# cpu.net
KiCad netlist of a schematic drawn in Altium Designer
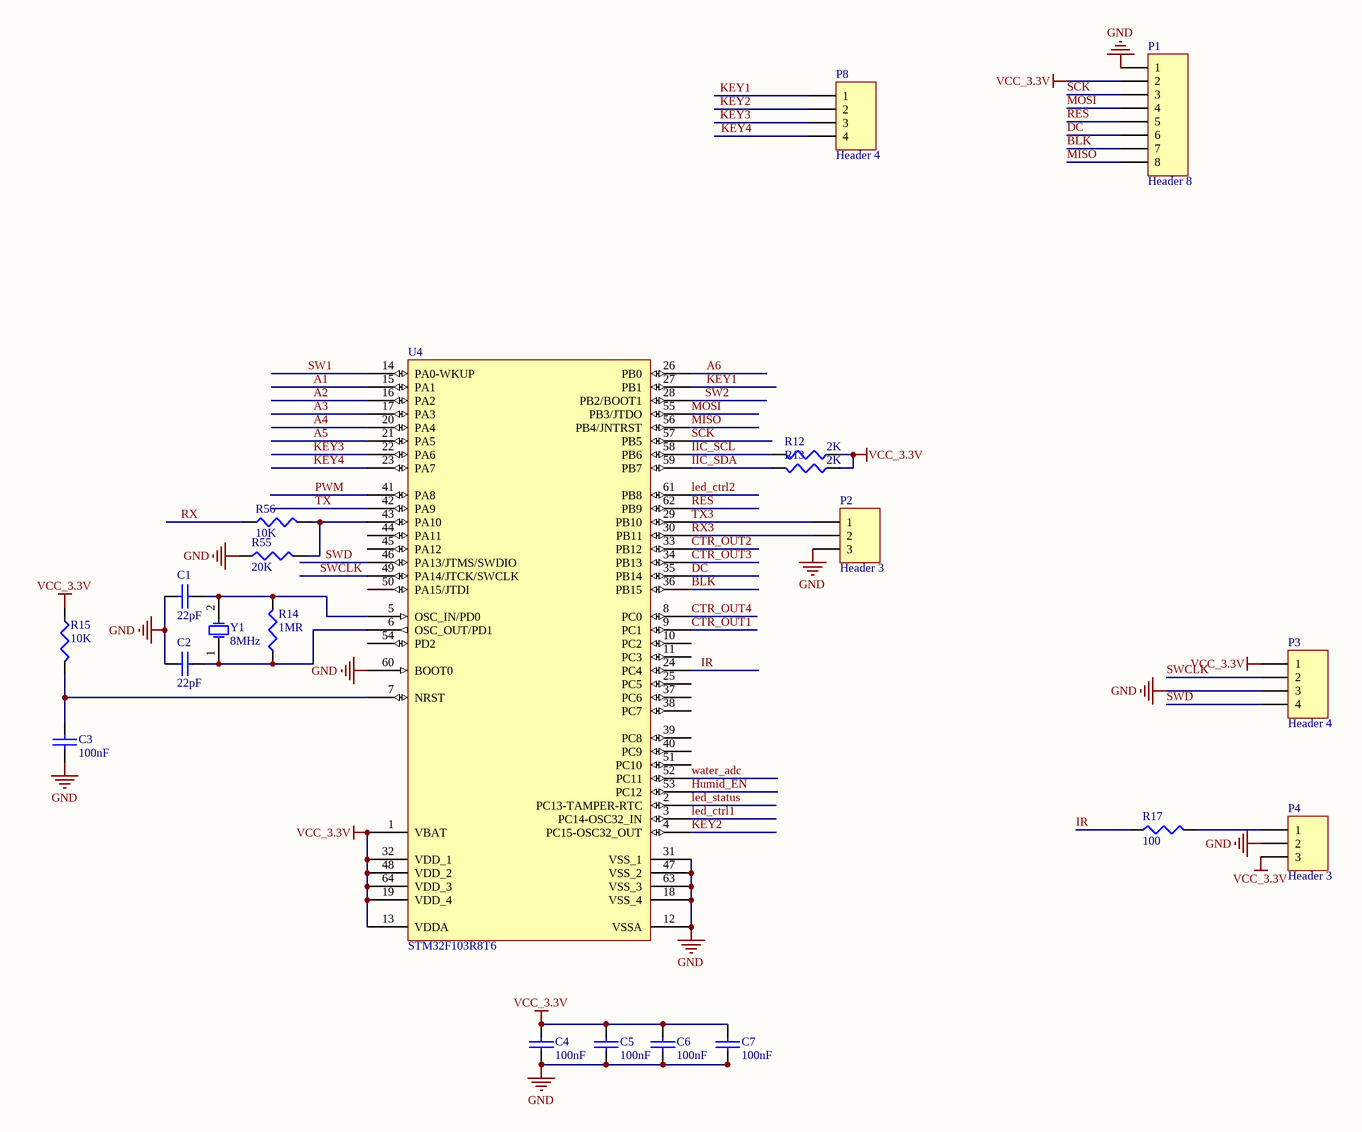
[diagram p0: cpu.SchDoc]

(export (version "E")
  (design (tool "Eeschema 10.0.6"))
  (components
    (comp (ref "C1")
      (value "22pF")
      (footprint "0805c")
      (description "Capacitor")
      (libsource (lib "SM") (part "CAP"))
    )
    (comp (ref "C2")
      (value "22pF")
      (footprint "0805c")
      (description "Capacitor")
      (libsource (lib "SM") (part "CAP"))
    )
    (comp (ref "C3")
      (value "100nF")
      (footprint "0805c")
      (description "Capacitor")
      (libsource (lib "SM") (part "CAP"))
    )
    (comp (ref "C4")
      (value "100nF")
      (footprint "0805c")
      (description "Capacitor")
      (libsource (lib "SM") (part "CAP"))
    )
    (comp (ref "C5")
      (value "100nF")
      (footprint "0805c")
      (description "Capacitor")
      (libsource (lib "SM") (part "CAP"))
    )
    (comp (ref "C6")
      (value "100nF")
      (footprint "0805c")
      (description "Capacitor")
      (libsource (lib "SM") (part "CAP"))
    )
    (comp (ref "C7")
      (value "100nF")
      (footprint "0805c")
      (description "Capacitor")
      (libsource (lib "SM") (part "CAP"))
    )
    (comp (ref "P1")
      (value "Header 8")
      (footprint "HDR1X8")
      (description "Header, 8-Pin")
      (fields (field (name "PUBLISHER") "Altium Limited"))
      (libsource (lib "Miscellaneous Connectors") (part "Header 8"))
    )
    (comp (ref "P2")
      (value "Header 3")
      (footprint "HDR1X3")
      (description "Header, 3-Pin")
      (fields (field (name "PUBLISHER") "Altium Limited"))
      (libsource (lib "Miscellaneous Connectors") (part "Header 3"))
    )
    (comp (ref "P3")
      (value "Header 4")
      (footprint "HDR1X4")
      (description "Header, 4-Pin")
      (fields (field (name "PUBLISHER") "Altium Limited"))
      (libsource (lib "Miscellaneous Connectors") (part "Header 4"))
    )
    (comp (ref "P4")
      (value "Header 3")
      (footprint "HDR1X3")
      (description "Header, 3-Pin")
      (fields (field (name "PUBLISHER") "Altium Limited"))
      (libsource (lib "Miscellaneous Connectors") (part "Header 3"))
    )
    (comp (ref "P8")
      (value "Header 4")
      (footprint "HDR1X4")
      (description "Header, 4-Pin")
      (fields (field (name "PUBLISHER") "Altium Limited"))
      (libsource (lib "Miscellaneous Connectors") (part "Header 4"))
    )
    (comp (ref "R12")
      (value "2K")
      (footprint "0805R")
      (description "Resistor")
      (fields (field (name "PUBLISHER") "Altium Limited"))
      (libsource (lib "SM") (part "Res3"))
    )
    (comp (ref "R13")
      (value "2K")
      (footprint "0805R")
      (description "Resistor")
      (fields (field (name "PUBLISHER") "Altium Limited"))
      (libsource (lib "SM") (part "Res3"))
    )
    (comp (ref "R14")
      (value "1MR")
      (footprint "0805R")
      (description "Resistor")
      (fields (field (name "PUBLISHER") "Altium Limited"))
      (libsource (lib "SM") (part "Res3"))
    )
    (comp (ref "R15")
      (value "10K")
      (footprint "0805R")
      (description "Resistor")
      (fields (field (name "PUBLISHER") "Altium Limited"))
      (libsource (lib "SM") (part "Res3"))
    )
    (comp (ref "R17")
      (value "100")
      (footprint "0805R")
      (description "Resistor")
      (fields (field (name "PUBLISHER") "Altium Limited"))
      (libsource (lib "SM") (part "Res3"))
    )
    (comp (ref "R55")
      (value "20K")
      (footprint "0805R")
      (description "Resistor")
      (fields (field (name "PUBLISHER") "Altium Limited"))
      (libsource (lib "SM") (part "Res3"))
    )
    (comp (ref "R56")
      (value "10K")
      (footprint "0805R")
      (description "Resistor")
      (fields (field (name "PUBLISHER") "Altium Limited"))
      (libsource (lib "SM") (part "Res3"))
    )
    (comp (ref "U4")
      (value "STM32F103R8T6")
      (footprint "LQFP-64")
      (description "STM32 ARM-based 32-bit MCU with 64 Kbytes Flash, 64-pin LQFP, Industrial Temperature")
      (fields (field (name "PUBLISHER") "Altium Limited"))
      (libsource (lib "ST Microcontroller 32-Bit STM32") (part "STM32F103R8T6"))
    )
    (comp (ref "Y1")
      (value "8MHz")
      (footprint "SMT5032")
      (description "Crystal Oscillator")
      (fields (field (name "PUBLISHER") "Altium Limited"))
      (libsource (lib "Miscellaneous Devices") (part "XTAL"))
    )
  )
  (nets
    (net (code "1") (name "/A1") (class "Default")
      (node (ref "U4") (pin "15") (pinfunction "PA1_15") (pintype "bidirectional"))
    )
    (net (code "2") (name "/A2") (class "Default")
      (node (ref "U4") (pin "16") (pinfunction "PA2_16") (pintype "bidirectional"))
    )
    (net (code "3") (name "/A3") (class "Default")
      (node (ref "U4") (pin "17") (pinfunction "PA3_17") (pintype "bidirectional"))
    )
    (net (code "4") (name "/A4") (class "Default")
      (node (ref "U4") (pin "20") (pinfunction "PA4_20") (pintype "bidirectional"))
    )
    (net (code "5") (name "/A5") (class "Default")
      (node (ref "U4") (pin "21") (pinfunction "PA5_21") (pintype "bidirectional"))
    )
    (net (code "6") (name "/A6") (class "Default")
      (node (ref "U4") (pin "26") (pinfunction "PB0_26") (pintype "bidirectional"))
    )
    (net (code "7") (name "/BLK") (class "Default")
      (node (ref "P1") (pin "7") (pinfunction "7_7") (pintype "passive"))
      (node (ref "U4") (pin "36") (pinfunction "PB15_36") (pintype "bidirectional"))
    )
    (net (code "8") (name "/CTR_OUT1") (class "Default")
      (node (ref "U4") (pin "9") (pinfunction "PC1_9") (pintype "bidirectional"))
    )
    (net (code "9") (name "/CTR_OUT2") (class "Default")
      (node (ref "U4") (pin "33") (pinfunction "PB12_33") (pintype "bidirectional"))
    )
    (net (code "10") (name "/CTR_OUT3") (class "Default")
      (node (ref "U4") (pin "34") (pinfunction "PB13_34") (pintype "bidirectional"))
    )
    (net (code "11") (name "/CTR_OUT4") (class "Default")
      (node (ref "U4") (pin "8") (pinfunction "PC0_8") (pintype "bidirectional"))
    )
    (net (code "12") (name "/DC") (class "Default")
      (node (ref "P1") (pin "6") (pinfunction "6_6") (pintype "passive"))
      (node (ref "U4") (pin "35") (pinfunction "PB14_35") (pintype "bidirectional"))
    )
    (net (code "13") (name "/Humid_EN") (class "Default")
      (node (ref "U4") (pin "53") (pinfunction "PC12_53") (pintype "bidirectional"))
    )
    (net (code "14") (name "/IIC_SCL") (class "Default")
      (node (ref "R12") (pin "2") (pinfunction "2_2") (pintype "passive"))
      (node (ref "U4") (pin "58") (pinfunction "PB6_58") (pintype "bidirectional"))
    )
    (net (code "15") (name "/IIC_SDA") (class "Default")
      (node (ref "R13") (pin "2") (pinfunction "2_2") (pintype "passive"))
      (node (ref "U4") (pin "59") (pinfunction "PB7_59") (pintype "bidirectional"))
    )
    (net (code "16") (name "/IR") (class "Default")
      (node (ref "R17") (pin "1") (pinfunction "1_1") (pintype "passive"))
      (node (ref "U4") (pin "24") (pinfunction "PC4_24") (pintype "bidirectional"))
    )
    (net (code "17") (name "/KEY1") (class "Default")
      (node (ref "P8") (pin "1") (pinfunction "1_1") (pintype "passive"))
      (node (ref "U4") (pin "27") (pinfunction "PB1_27") (pintype "bidirectional"))
    )
    (net (code "18") (name "/KEY2") (class "Default")
      (node (ref "P8") (pin "2") (pinfunction "2_2") (pintype "passive"))
      (node (ref "U4") (pin "4") (pinfunction "PC15-OSC32_OUT_4") (pintype "bidirectional"))
    )
    (net (code "19") (name "/KEY3") (class "Default")
      (node (ref "P8") (pin "3") (pinfunction "3_3") (pintype "passive"))
      (node (ref "U4") (pin "22") (pinfunction "PA6_22") (pintype "bidirectional"))
    )
    (net (code "20") (name "/KEY4") (class "Default")
      (node (ref "P8") (pin "4") (pinfunction "4_4") (pintype "passive"))
      (node (ref "U4") (pin "23") (pinfunction "PA7_23") (pintype "bidirectional"))
    )
    (net (code "21") (name "/MISO") (class "Default")
      (node (ref "P1") (pin "8") (pinfunction "8_8") (pintype "passive"))
      (node (ref "U4") (pin "56") (pinfunction "PB4/JNTRST_56") (pintype "bidirectional"))
    )
    (net (code "22") (name "/MOSI") (class "Default")
      (node (ref "P1") (pin "4") (pinfunction "4_4") (pintype "passive"))
      (node (ref "U4") (pin "55") (pinfunction "PB3/JTDO_55") (pintype "bidirectional"))
    )
    (net (code "23") (name "/PWM") (class "Default")
      (node (ref "U4") (pin "41") (pinfunction "PA8_41") (pintype "bidirectional"))
    )
    (net (code "24") (name "/RES") (class "Default")
      (node (ref "P1") (pin "5") (pinfunction "5_5") (pintype "passive"))
      (node (ref "U4") (pin "62") (pinfunction "PB9_62") (pintype "bidirectional"))
    )
    (net (code "25") (name "/RX") (class "Default")
      (node (ref "R56") (pin "1") (pinfunction "1_1") (pintype "passive"))
    )
    (net (code "26") (name "/RX3") (class "Default")
      (node (ref "P2") (pin "2") (pinfunction "2_2") (pintype "passive"))
      (node (ref "U4") (pin "30") (pinfunction "PB11_30") (pintype "bidirectional"))
    )
    (net (code "27") (name "/SCK") (class "Default")
      (node (ref "P1") (pin "3") (pinfunction "3_3") (pintype "passive"))
      (node (ref "U4") (pin "57") (pinfunction "PB5_57") (pintype "bidirectional"))
    )
    (net (code "28") (name "/SW1") (class "Default")
      (node (ref "U4") (pin "14") (pinfunction "PA0-WKUP_14") (pintype "bidirectional"))
    )
    (net (code "29") (name "/SW2") (class "Default")
      (node (ref "U4") (pin "28") (pinfunction "PB2/BOOT1_28") (pintype "bidirectional"))
    )
    (net (code "30") (name "/SWCLK") (class "Default")
      (node (ref "P3") (pin "2") (pinfunction "2_2") (pintype "passive"))
      (node (ref "U4") (pin "49") (pinfunction "PA14/JTCK/SWCLK_49") (pintype "bidirectional"))
    )
    (net (code "31") (name "/SWD") (class "Default")
      (node (ref "P3") (pin "4") (pinfunction "4_4") (pintype "passive"))
      (node (ref "U4") (pin "46") (pinfunction "PA13/JTMS/SWDIO_46") (pintype "bidirectional"))
    )
    (net (code "32") (name "/TX") (class "Default")
      (node (ref "U4") (pin "42") (pinfunction "PA9_42") (pintype "bidirectional"))
    )
    (net (code "33") (name "/TX3") (class "Default")
      (node (ref "P2") (pin "1") (pinfunction "1_1") (pintype "passive"))
      (node (ref "U4") (pin "29") (pinfunction "PB10_29") (pintype "bidirectional"))
    )
    (net (code "34") (name "/led_ctrl1") (class "Default")
      (node (ref "U4") (pin "3") (pinfunction "PC14-OSC32_IN_3") (pintype "bidirectional"))
    )
    (net (code "35") (name "/led_ctrl2") (class "Default")
      (node (ref "U4") (pin "61") (pinfunction "PB8_61") (pintype "bidirectional"))
    )
    (net (code "36") (name "/led_status") (class "Default")
      (node (ref "U4") (pin "2") (pinfunction "PC13-TAMPER-RTC_2") (pintype "bidirectional"))
    )
    (net (code "37") (name "/water_adc") (class "Default")
      (node (ref "U4") (pin "52") (pinfunction "PC11_52") (pintype "bidirectional"))
    )
    (net (code "38") (name "GND") (class "Default")
      (node (ref "C1") (pin "1") (pinfunction "1_1") (pintype "passive"))
      (node (ref "C2") (pin "1") (pinfunction "1_1") (pintype "passive"))
      (node (ref "C3") (pin "1") (pinfunction "1_1") (pintype "passive"))
      (node (ref "C4") (pin "1") (pinfunction "1_1") (pintype "passive"))
      (node (ref "C5") (pin "1") (pinfunction "1_1") (pintype "passive"))
      (node (ref "C6") (pin "1") (pinfunction "1_1") (pintype "passive"))
      (node (ref "C7") (pin "1") (pinfunction "1_1") (pintype "passive"))
      (node (ref "P1") (pin "1") (pinfunction "1_1") (pintype "passive"))
      (node (ref "P2") (pin "3") (pinfunction "3_3") (pintype "passive"))
      (node (ref "P3") (pin "3") (pinfunction "3_3") (pintype "passive"))
      (node (ref "P4") (pin "2") (pinfunction "2_2") (pintype "passive"))
      (node (ref "R55") (pin "1") (pinfunction "1_1") (pintype "passive"))
      (node (ref "U4") (pin "12") (pinfunction "VSSA_12") (pintype "power_in"))
      (node (ref "U4") (pin "18") (pinfunction "VSS_4_18") (pintype "power_in"))
      (node (ref "U4") (pin "31") (pinfunction "VSS_1_31") (pintype "power_in"))
      (node (ref "U4") (pin "47") (pinfunction "VSS_2_47") (pintype "power_in"))
      (node (ref "U4") (pin "60") (pinfunction "BOOT0_60") (pintype "input"))
      (node (ref "U4") (pin "63") (pinfunction "VSS_3_63") (pintype "power_in"))
    )
    (net (code "39") (name "Net-(P4-Pad1)") (class "Default")
      (node (ref "P4") (pin "1") (pinfunction "1_1") (pintype "passive"))
      (node (ref "R17") (pin "2") (pinfunction "2_2") (pintype "passive"))
    )
    (net (code "40") (name "Net-(U4-NRST)") (class "Default")
      (node (ref "C3") (pin "2") (pinfunction "2_2") (pintype "passive"))
      (node (ref "R15") (pin "2") (pinfunction "2_2") (pintype "passive"))
      (node (ref "U4") (pin "7") (pinfunction "NRST_7") (pintype "bidirectional"))
    )
    (net (code "41") (name "Net-(U4-OSC_IN{slash}PD0)") (class "Default")
      (node (ref "C1") (pin "2") (pinfunction "2_2") (pintype "passive"))
      (node (ref "R14") (pin "2") (pinfunction "2_2") (pintype "passive"))
      (node (ref "U4") (pin "5") (pinfunction "OSC_IN/PD0_5") (pintype "input"))
      (node (ref "Y1") (pin "2") (pinfunction "OSC2_2") (pintype "passive"))
    )
    (net (code "42") (name "Net-(U4-OSC_OUT{slash}PD1)") (class "Default")
      (node (ref "C2") (pin "2") (pinfunction "2_2") (pintype "passive"))
      (node (ref "R14") (pin "1") (pinfunction "1_1") (pintype "passive"))
      (node (ref "U4") (pin "6") (pinfunction "OSC_OUT/PD1_6") (pintype "output"))
      (node (ref "Y1") (pin "1") (pinfunction "OSC1_1") (pintype "passive"))
    )
    (net (code "43") (name "Net-(U4-PA10)") (class "Default")
      (node (ref "R55") (pin "2") (pinfunction "2_2") (pintype "passive"))
      (node (ref "R56") (pin "2") (pinfunction "2_2") (pintype "passive"))
      (node (ref "U4") (pin "43") (pinfunction "PA10_43") (pintype "bidirectional"))
    )
    (net (code "44") (name "VCC_3.3V") (class "Default")
      (node (ref "C4") (pin "2") (pinfunction "2_2") (pintype "passive"))
      (node (ref "C5") (pin "2") (pinfunction "2_2") (pintype "passive"))
      (node (ref "C6") (pin "2") (pinfunction "2_2") (pintype "passive"))
      (node (ref "C7") (pin "2") (pinfunction "2_2") (pintype "passive"))
      (node (ref "P1") (pin "2") (pinfunction "2_2") (pintype "passive"))
      (node (ref "P3") (pin "1") (pinfunction "1_1") (pintype "passive"))
      (node (ref "P4") (pin "3") (pinfunction "3_3") (pintype "passive"))
      (node (ref "R12") (pin "1") (pinfunction "1_1") (pintype "passive"))
      (node (ref "R13") (pin "1") (pinfunction "1_1") (pintype "passive"))
      (node (ref "R15") (pin "1") (pinfunction "1_1") (pintype "passive"))
      (node (ref "U4") (pin "1") (pinfunction "VBAT_1") (pintype "power_in"))
      (node (ref "U4") (pin "13") (pinfunction "VDDA_13") (pintype "power_in"))
      (node (ref "U4") (pin "19") (pinfunction "VDD_4_19") (pintype "power_in"))
      (node (ref "U4") (pin "32") (pinfunction "VDD_1_32") (pintype "power_in"))
      (node (ref "U4") (pin "48") (pinfunction "VDD_2_48") (pintype "power_in"))
      (node (ref "U4") (pin "64") (pinfunction "VDD_3_64") (pintype "power_in"))
    )
    (net (code "45") (name "unconnected-(U4-PA11-Pad44)") (class "Default")
      (node (ref "U4") (pin "44") (pinfunction "PA11_44") (pintype "bidirectional"))
    )
    (net (code "46") (name "unconnected-(U4-PA12-Pad45)") (class "Default")
      (node (ref "U4") (pin "45") (pinfunction "PA12_45") (pintype "bidirectional"))
    )
    (net (code "47") (name "unconnected-(U4-PA15{slash}JTDI-Pad50)") (class "Default")
      (node (ref "U4") (pin "50") (pinfunction "PA15/JTDI_50") (pintype "bidirectional"))
    )
    (net (code "48") (name "unconnected-(U4-PC2-Pad10)") (class "Default")
      (node (ref "U4") (pin "10") (pinfunction "PC2_10") (pintype "bidirectional"))
    )
    (net (code "49") (name "unconnected-(U4-PC3-Pad11)") (class "Default")
      (node (ref "U4") (pin "11") (pinfunction "PC3_11") (pintype "bidirectional"))
    )
    (net (code "50") (name "unconnected-(U4-PC5-Pad25)") (class "Default")
      (node (ref "U4") (pin "25") (pinfunction "PC5_25") (pintype "bidirectional"))
    )
    (net (code "51") (name "unconnected-(U4-PC6-Pad37)") (class "Default")
      (node (ref "U4") (pin "37") (pinfunction "PC6_37") (pintype "bidirectional"))
    )
    (net (code "52") (name "unconnected-(U4-PC7-Pad38)") (class "Default")
      (node (ref "U4") (pin "38") (pinfunction "PC7_38") (pintype "bidirectional"))
    )
    (net (code "53") (name "unconnected-(U4-PC8-Pad39)") (class "Default")
      (node (ref "U4") (pin "39") (pinfunction "PC8_39") (pintype "bidirectional"))
    )
    (net (code "54") (name "unconnected-(U4-PC9-Pad40)") (class "Default")
      (node (ref "U4") (pin "40") (pinfunction "PC9_40") (pintype "bidirectional"))
    )
    (net (code "55") (name "unconnected-(U4-PC10-Pad51)") (class "Default")
      (node (ref "U4") (pin "51") (pinfunction "PC10_51") (pintype "bidirectional"))
    )
    (net (code "56") (name "unconnected-(U4-PD2-Pad54)") (class "Default")
      (node (ref "U4") (pin "54") (pinfunction "PD2_54") (pintype "bidirectional"))
    )
  )
)
